# Off-Line_3W_Non_Isolated_Power_Supply.net
KiCad netlist of a schematic drawn in Altium Designer
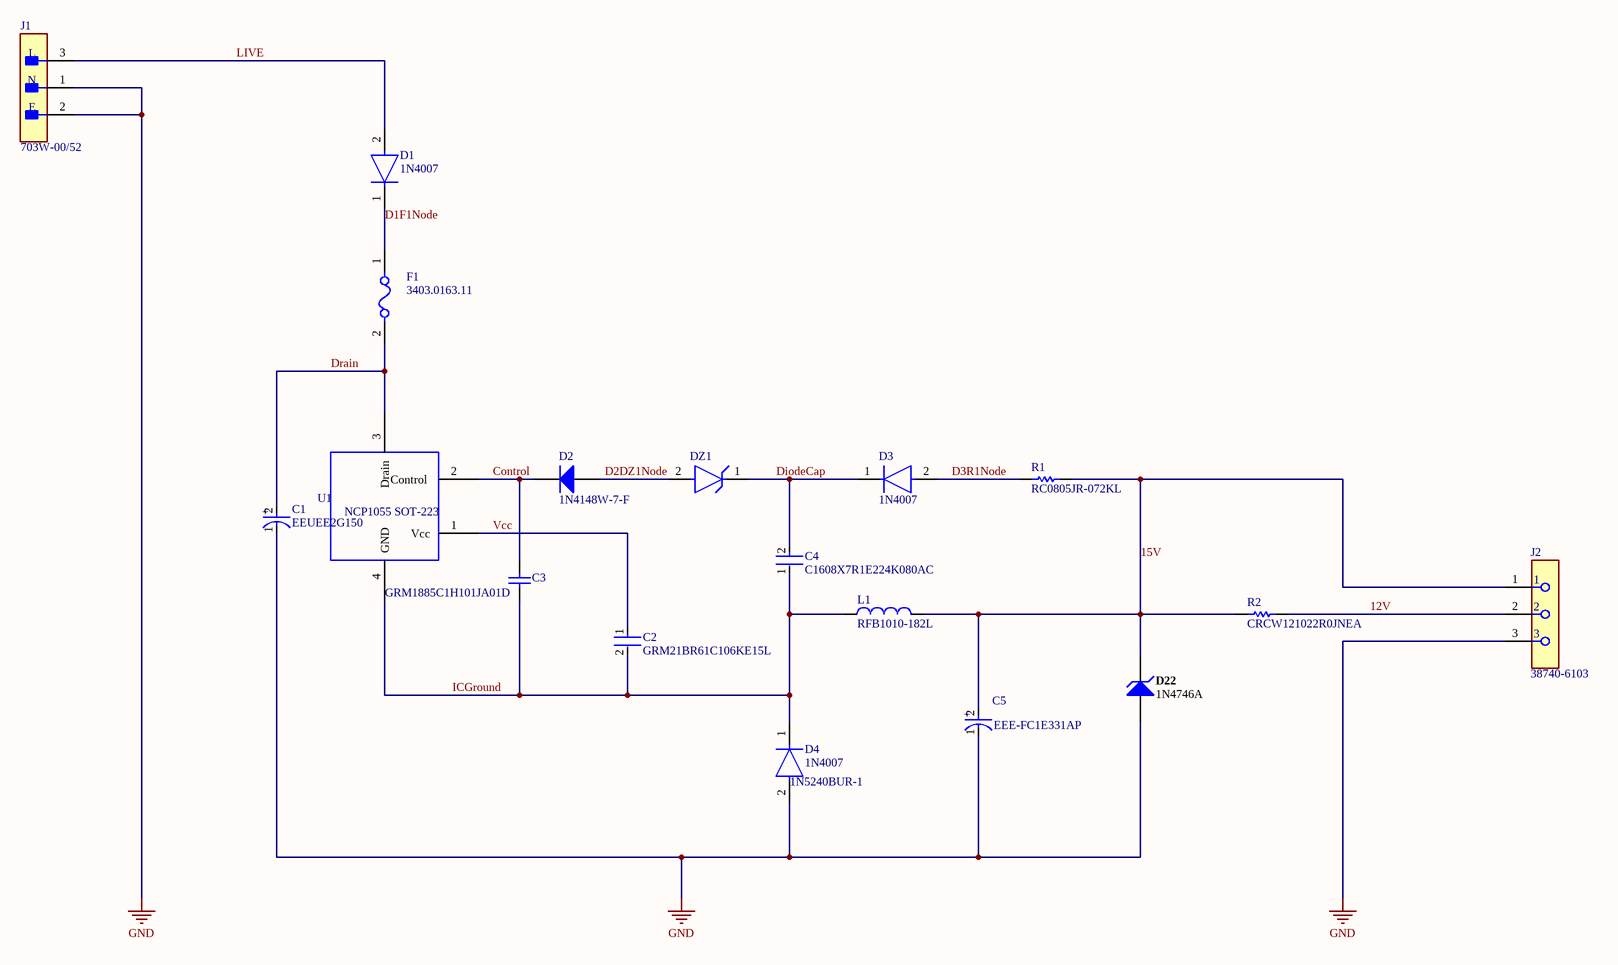
[diagram p0: Off-Line 3W Non Isolated Power Supply.SchDoc]

(export (version "E")
  (design (tool "Eeschema 10.0.6"))
  (components
    (comp (ref "C1")
      (value "EEUEE2G150")
      (footprint "FP-RAD-TH-D_12_5_0_5-L_20-MFG")
      (description "Aluminum Electrolytic Capacitors (Radial Lead Type) 15uF ±20% 400V")
      (fields (field (name "VOLTAGE") "400V") (field (name "TOLERANCE") "20%"))
      (libsource (lib "Altium Content Vault") (part "a00bbbee19879c290e62620ae7e47b1"))
    )
    (comp (ref "C2")
      (value "GRM21BR61C106KE15L")
      (footprint "FP-GRM21B-0_1-IPC_C")
      (description "Chip Multilayer Ceramic Capacitors for General Purpose, 0805, 10uF, X5R, 15%, 10%, 16V")
      (fields (field (name "TOLERANCE") "10%") (field (name "VOLTAGE") "16V"))
      (libsource (lib "Altium Content Vault") (part "b4654b650e69147ec39a6b967a45e02"))
    )
    (comp (ref "C3")
      (value "GRM1885C1H101JA01D")
      (footprint "CAPC1608X90X35NL10T15")
      (fields (field (name "MANUFACTURER") "Murata"))
      (libsource (lib "Altium Content Vault") (part "CAP"))
    )
    (comp (ref "C4")
      (value "C1608X7R1E224K080AC")
      (footprint "FP-C1608-080-0_1-IPC_B")
      (description "Multilayer Ceramic Capacitors 220nF ±10% 25V X7R SMD 0603")
      (fields (field (name "TOLERANCE") "10%"))
      (libsource (lib "Altium Content Vault") (part "236180d848d6139a670b325ea6854c9"))
    )
    (comp (ref "C5")
      (value "EEE-FC1E331AP")
      (footprint "FP-FC-G-MFG")
      (description "CAP ALUM 330UF 20% 25V SMD")
      (fields (field (name "TOLERANCE") "20%") (field (name "VOLTAGE") "25V"))
      (libsource (lib "Altium Content Vault") (part "203bc49f2ac43e59fd269a8c329ed05"))
    )
    (comp (ref "D1")
      (value "1N4007")
      (footprint "FP-1N4007-MFG")
      (description "Rectifier diode 1000 V 1 A DO-41, ,")
      (fields
        (field (name "MANUFACTURER") "Diotec")
        (field (name "OCTOPART") "https://octopart.com/1n4007-diotec-4040411")
      )
      (libsource (lib "Altium Content Vault") (part "d7152d700b627762746794eb795d46e"))
    )
    (comp (ref "D2")
      (value "1N4148W-7-F")
      (footprint "DIOD-SOD123-2_V")
      (description "Fast Switching Diode, 100 V, 0.15 A, -65 to 150 degC, 2-Pin?SOD123, RoHS, Tape and Reel")
      (fields (field (name "MANUFACTURER") "DiodesIncorporated"))
      (libsource (lib "Altium Content Vault") (part "D-AK-2"))
    )
    (comp (ref "D3")
      (value "1N4007")
      (footprint "FP-1N4007-MFG")
      (description "Rectifier diode 1000 V 1 A DO-41, ,")
      (fields
        (field (name "MANUFACTURER") "Diotec")
        (field (name "OCTOPART") "https://octopart.com/1n4007-diotec-4040411")
      )
      (libsource (lib "Altium Content Vault") (part "d7152d700b627762746794eb795d46e"))
    )
    (comp (ref "D4")
      (value "1N4007")
      (footprint "FP-1N4007-MFG")
      (description "Rectifier diode 1000 V 1 A DO-41, ,")
      (fields
        (field (name "MANUFACTURER") "Diotec")
        (field (name "OCTOPART") "https://octopart.com/1n4007-diotec-4040411")
      )
      (libsource (lib "Altium Content Vault") (part "d7152d700b627762746794eb795d46e"))
    )
    (comp (ref "D22")
      (value "1N4746A")
      (footprint "FAIR-DO-41-2_V")
      (description "Zener Diode, 18V, 1W, 5%, -65 to 200 degC, 2-Pin DO-41, Body 2.72 x 5.2 mm, RoHS")
      (fields (field (name "TOLERANCE") "5%") (field (name "MANUFACTURER") "Fairchild Semiconductor"))
      (libsource (lib "Altium Content Vault") (part "FAIR-DZEN-A1K2-2"))
    )
    (comp (ref "DZ1")
      (value "1N5240BUR-1")
      (footprint "FP-DO-213AA-MFG")
      (description "DIODE ZENER")
      (libsource (lib "Altium Content Vault") (part "f813f71cba58e380607f5dd3caf9714"))
    )
    (comp (ref "F1")
      (value "3403.0163.11")
      (footprint "FP-3403_0163_11-MFG")
      (description "FUSE BRD MNT 500MA 250VAC 125VDC")
      (fields
        (field (name "OCTOPART") "https://octopart.com/3403.0163.11-schurter-65395")
        (field (name "MANUFACTURER") "Schurter Inc")
      )
      (libsource (lib "Altium Content Vault") (part "5bcf9b9f640e542cf0359d10258e979"))
    )
    (comp (ref "J1")
      (value "703W-00/52")
      (footprint "FP-703W-00-52-MFG")
      (description "PWR ENT RCPT IEC320-C14 PNL SLDR")
      (libsource (lib "Altium Content Vault") (part "d3fa5aafac2488dd744475722bda3d4"))
    )
    (comp (ref "J2")
      (value "38740-6103")
      (footprint "FP-38740-6103-MFG")
      (libsource (lib "Altium Content Vault") (part "00ca6c5c4da8d80882129699458ab53"))
    )
    (comp (ref "L1")
      (value "RFB1010-182L")
      (footprint "COIL-RFB1010-2_V")
      (fields (field (name "TOLERANCE") "10%") (field (name "MANUFACTURER") "Coilcraft"))
      (libsource (lib "Altium Content Vault") (part "COIL-IND-2"))
    )
    (comp (ref "R1")
      (value "RC0805JR-072KL")
      (footprint "RESC2013X60X35ML10T20")
      (fields (field (name "MANUFACTURER") "Yageo"))
      (libsource (lib "Altium Content Vault") (part "RES"))
    )
    (comp (ref "R2")
      (value "CRCW121022R0JNEA")
      (footprint "RESC3225X60X45ML20T20")
      (fields (field (name "MANUFACTURER") "Vishay Dale"))
      (libsource (lib "Altium Content Vault") (part "RES"))
    )
    (comp (ref "U1")
      (value "NCP1055 SOT-223")
      (footprint "NCP1055 SOT-223")
      (libsource (lib "3W Supply") (part "NCP1055 SOT-223"))
    )
  )
  (nets
    (net (code "1") (name "/12V") (class "Default")
      (node (ref "J2") (pin "2") (pinfunction "2_2") (pintype "passive"))
      (node (ref "R2") (pin "2") (pinfunction "2_2") (pintype "passive"))
    )
    (net (code "2") (name "/15V") (class "Default")
      (node (ref "C5") (pin "2") (pinfunction "A_2") (pintype "passive"))
      (node (ref "D22") (pin "2") (pinfunction "K_2") (pintype "passive"))
      (node (ref "J2") (pin "1") (pinfunction "1_1") (pintype "passive"))
      (node (ref "L1") (pin "2") (pinfunction "2_2") (pintype "passive"))
      (node (ref "R1") (pin "2") (pinfunction "2_2") (pintype "passive"))
      (node (ref "R2") (pin "1") (pinfunction "1_1") (pintype "passive"))
    )
    (net (code "3") (name "/Control") (class "Default")
      (node (ref "C3") (pin "2") (pinfunction "2_2") (pintype "passive"))
      (node (ref "D2") (pin "2") (pinfunction "K_2") (pintype "passive"))
      (node (ref "U1") (pin "2") (pinfunction "Control_2") (pintype "passive"))
    )
    (net (code "4") (name "/D1F1Node") (class "Default")
      (node (ref "D1") (pin "1") (pinfunction "C_1") (pintype "passive"))
      (node (ref "F1") (pin "1") (pinfunction "1_1") (pintype "passive"))
    )
    (net (code "5") (name "/D2DZ1Node") (class "Default")
      (node (ref "D2") (pin "1") (pinfunction "A_1") (pintype "passive"))
      (node (ref "DZ1") (pin "2") (pinfunction "A_2") (pintype "passive"))
    )
    (net (code "6") (name "/D3R1Node") (class "Default")
      (node (ref "D3") (pin "2") (pinfunction "A_2") (pintype "passive"))
      (node (ref "R1") (pin "1") (pinfunction "1_1") (pintype "passive"))
    )
    (net (code "7") (name "/DiodeCap") (class "Default")
      (node (ref "C4") (pin "2") (pinfunction "2_2") (pintype "passive"))
      (node (ref "D3") (pin "1") (pinfunction "C_1") (pintype "passive"))
      (node (ref "DZ1") (pin "1") (pinfunction "C_1") (pintype "passive"))
    )
    (net (code "8") (name "/Drain") (class "Default")
      (node (ref "C1") (pin "2") (pinfunction "A_2") (pintype "passive"))
      (node (ref "F1") (pin "2") (pinfunction "2_2") (pintype "passive"))
      (node (ref "U1") (pin "3") (pinfunction "Drain_3") (pintype "passive"))
    )
    (net (code "9") (name "/ICGround") (class "Default")
      (node (ref "C2") (pin "2") (pinfunction "2_2") (pintype "passive"))
      (node (ref "C3") (pin "1") (pinfunction "1_1") (pintype "passive"))
      (node (ref "C4") (pin "1") (pinfunction "1_1") (pintype "passive"))
      (node (ref "D4") (pin "1") (pinfunction "C_1") (pintype "passive"))
      (node (ref "L1") (pin "1") (pinfunction "1_1") (pintype "passive"))
      (node (ref "U1") (pin "4") (pinfunction "GND_4") (pintype "passive"))
    )
    (net (code "10") (name "/LIVE") (class "Default")
      (node (ref "D1") (pin "2") (pinfunction "A_2") (pintype "passive"))
      (node (ref "J1") (pin "3") (pinfunction "L_3") (pintype "passive"))
    )
    (net (code "11") (name "/Vcc") (class "Default")
      (node (ref "C2") (pin "1") (pinfunction "1_1") (pintype "passive"))
      (node (ref "U1") (pin "1") (pinfunction "Vcc_1") (pintype "passive"))
    )
    (net (code "12") (name "GND") (class "Default")
      (node (ref "C1") (pin "1") (pinfunction "C_1") (pintype "passive"))
      (node (ref "C5") (pin "1") (pinfunction "C_1") (pintype "passive"))
      (node (ref "D22") (pin "1") (pinfunction "A_1") (pintype "passive"))
      (node (ref "D4") (pin "2") (pinfunction "A_2") (pintype "passive"))
      (node (ref "J1") (pin "1") (pinfunction "N_1") (pintype "passive"))
      (node (ref "J1") (pin "2") (pinfunction "E_2") (pintype "passive"))
      (node (ref "J2") (pin "3") (pinfunction "3_3") (pintype "passive"))
    )
  )
)
